# pi_day_2025.net
KiCad netlist of a schematic drawn in EAGLE
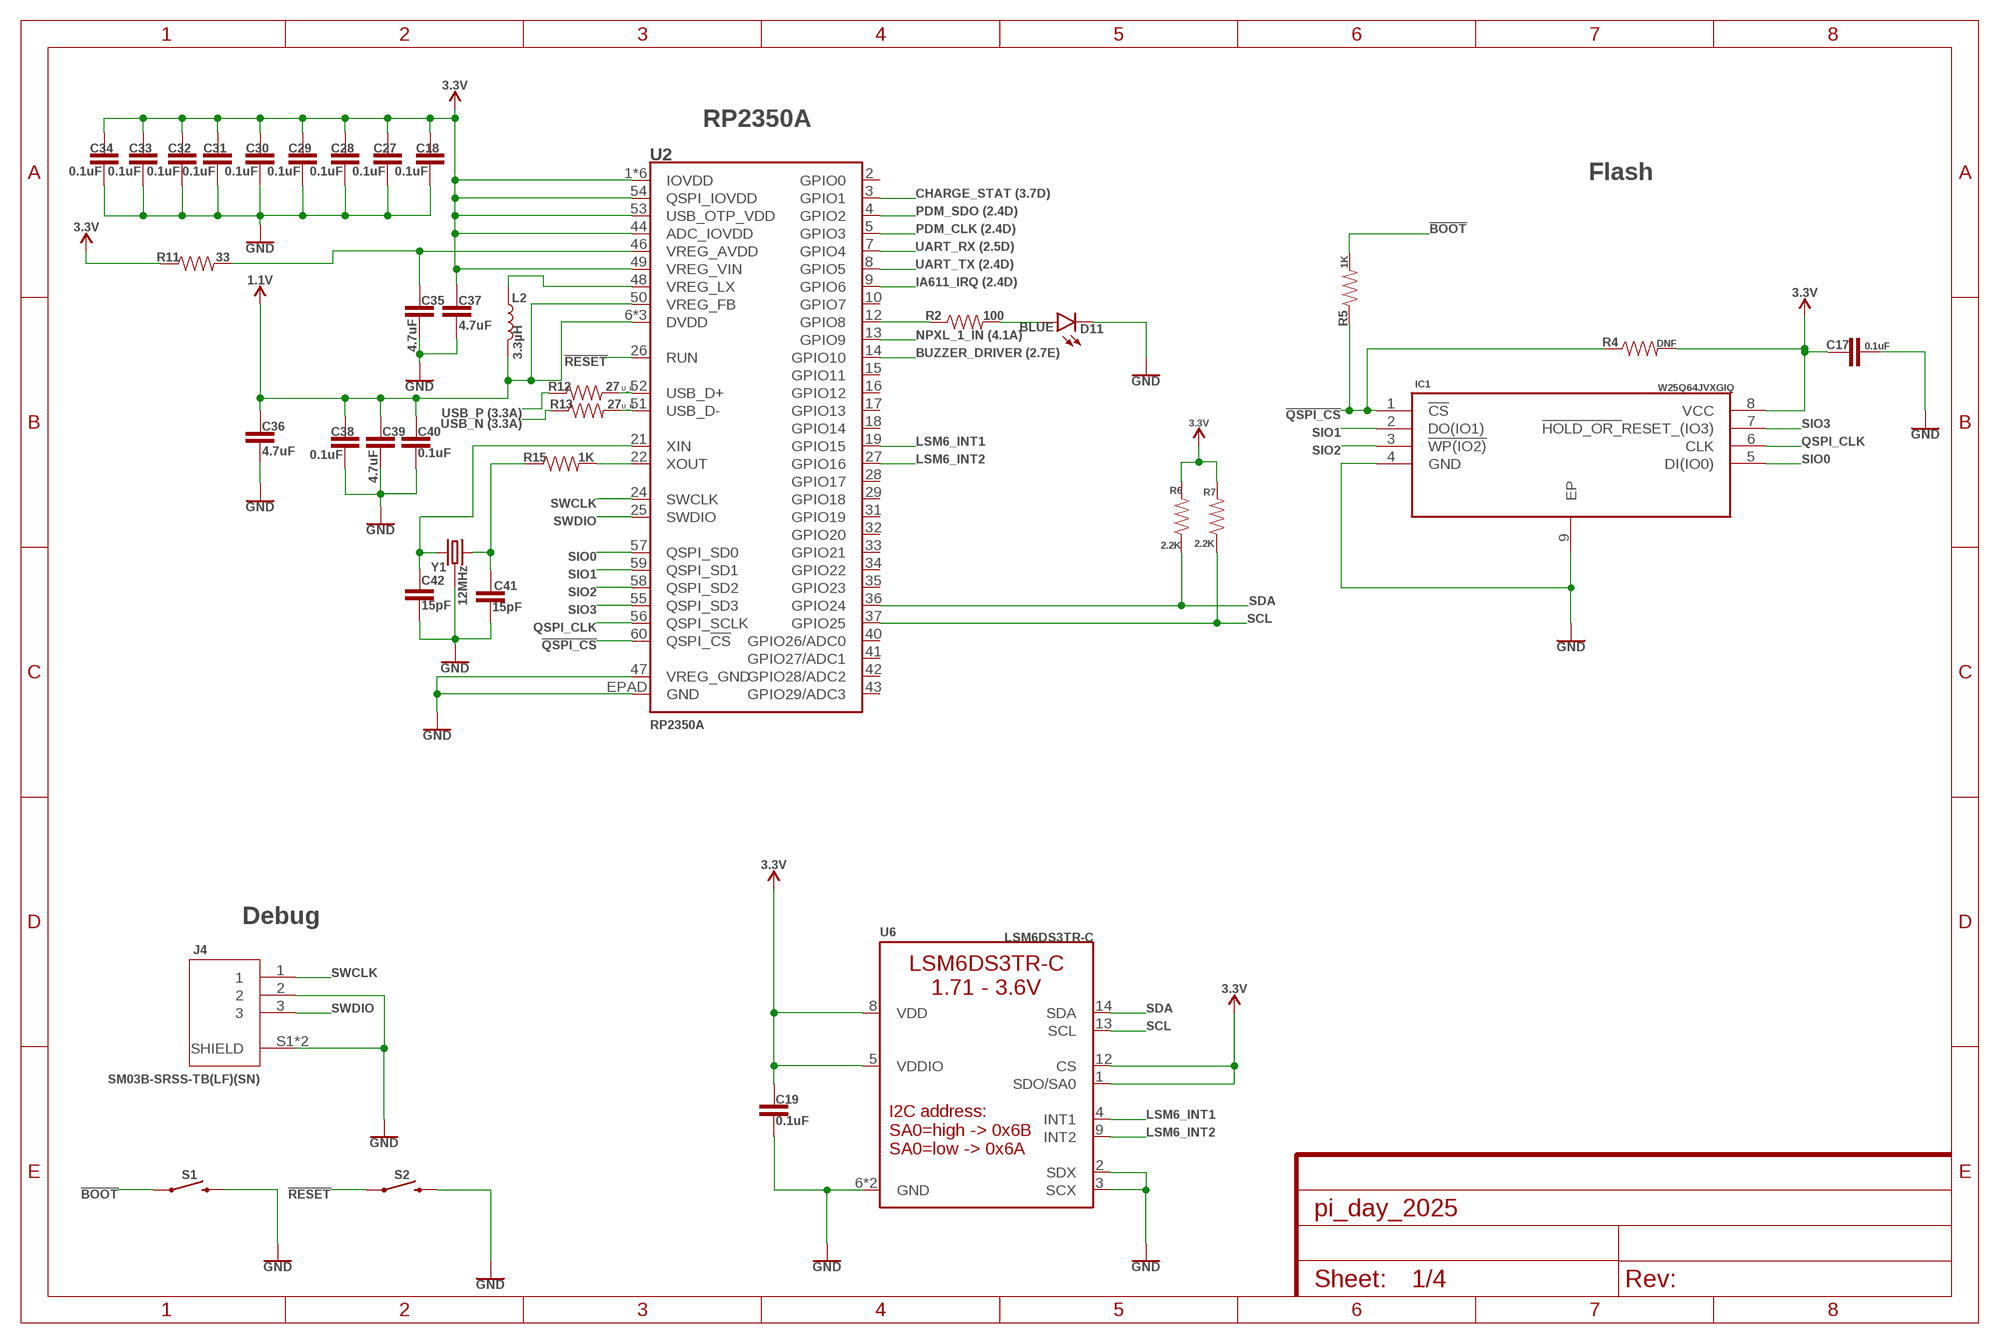
[diagram p0: schematic, sheet 1]
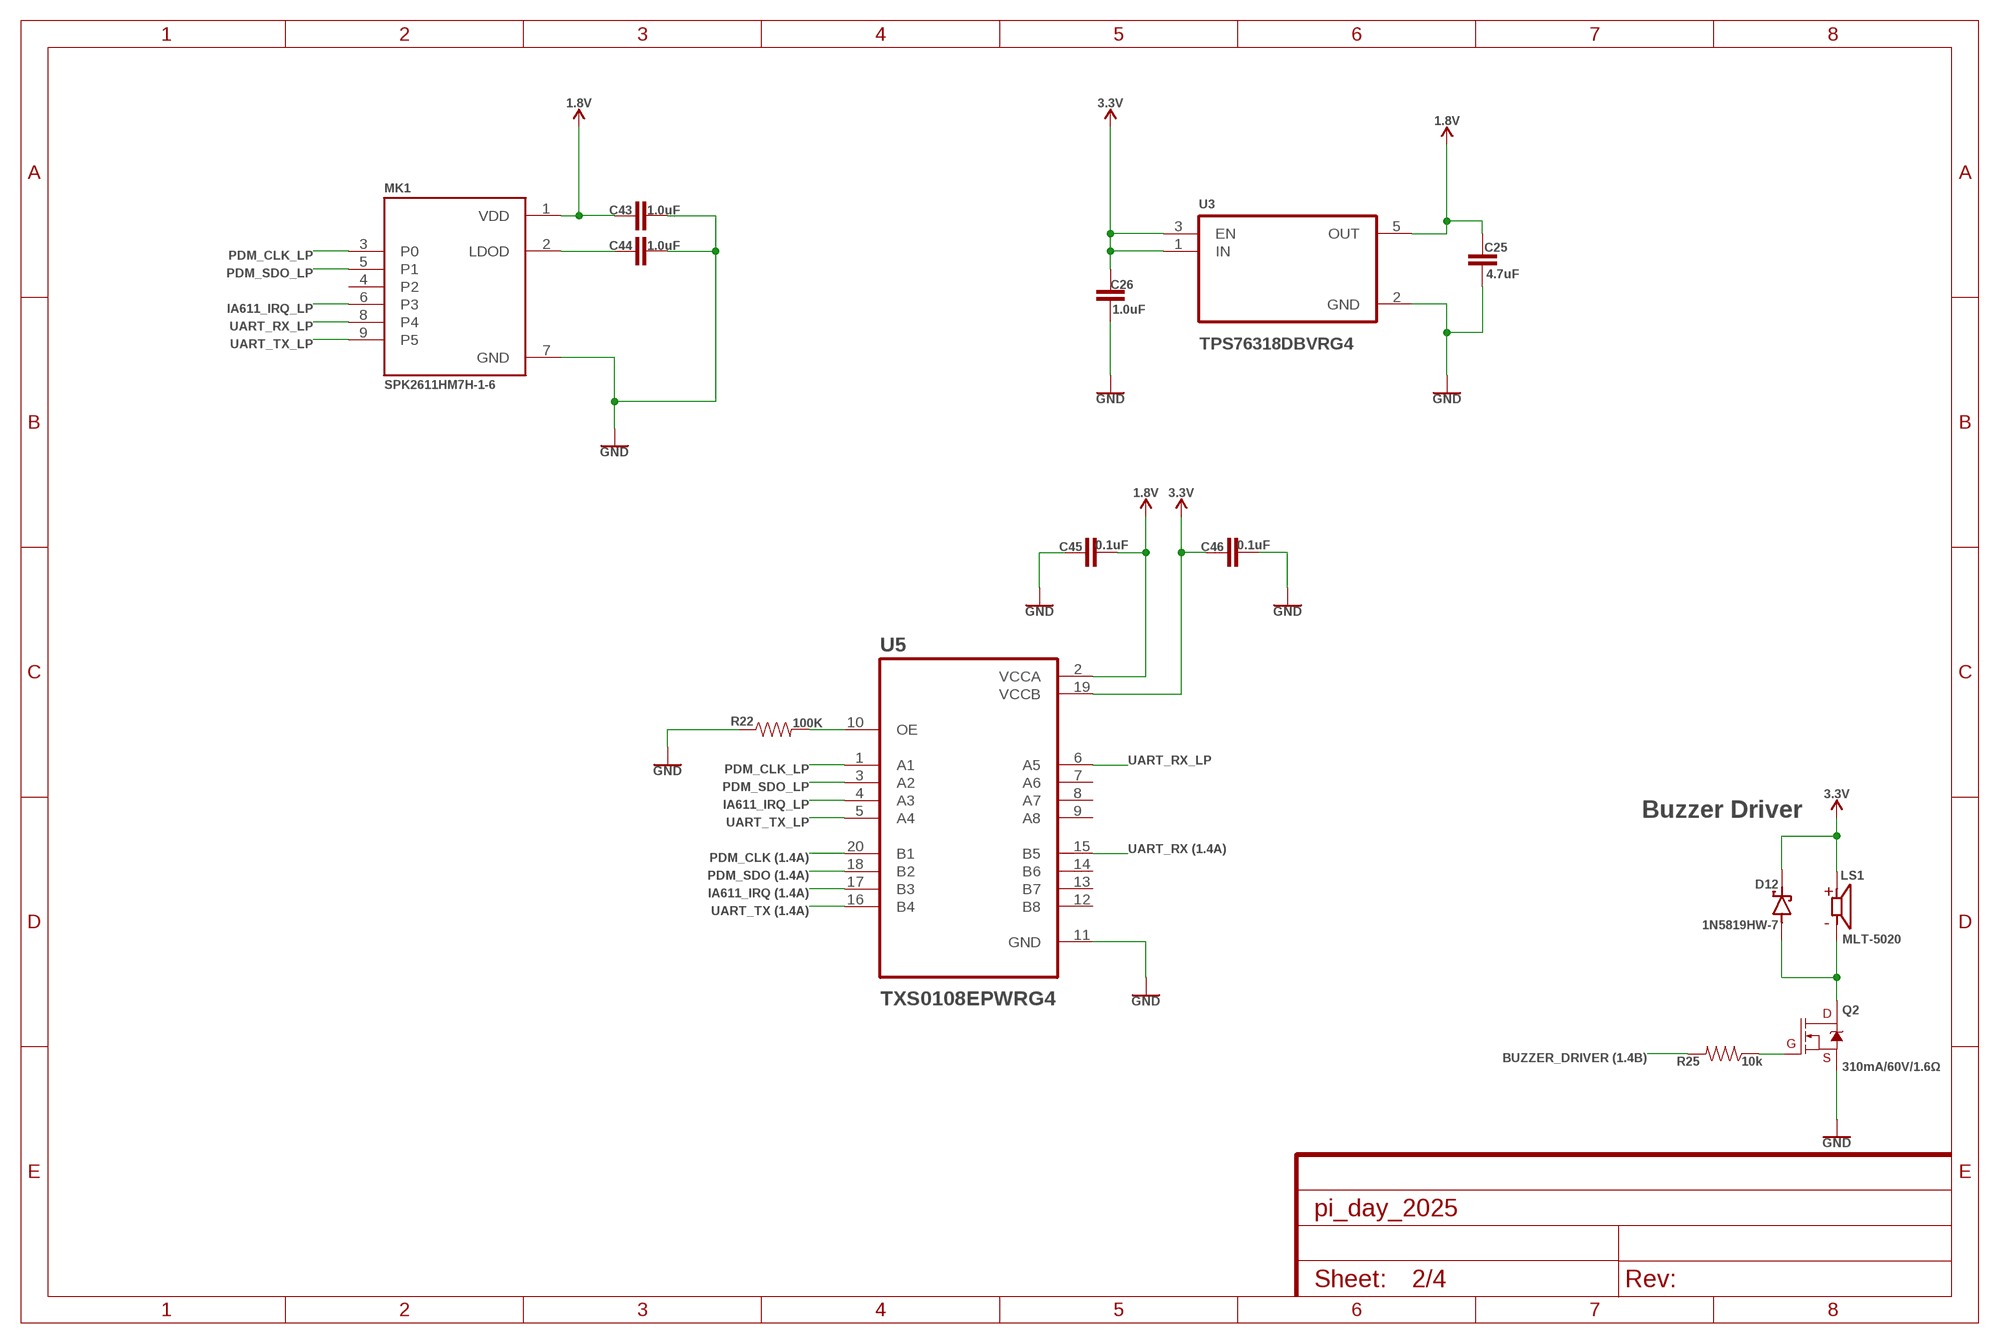
[diagram p1: schematic, sheet 2]
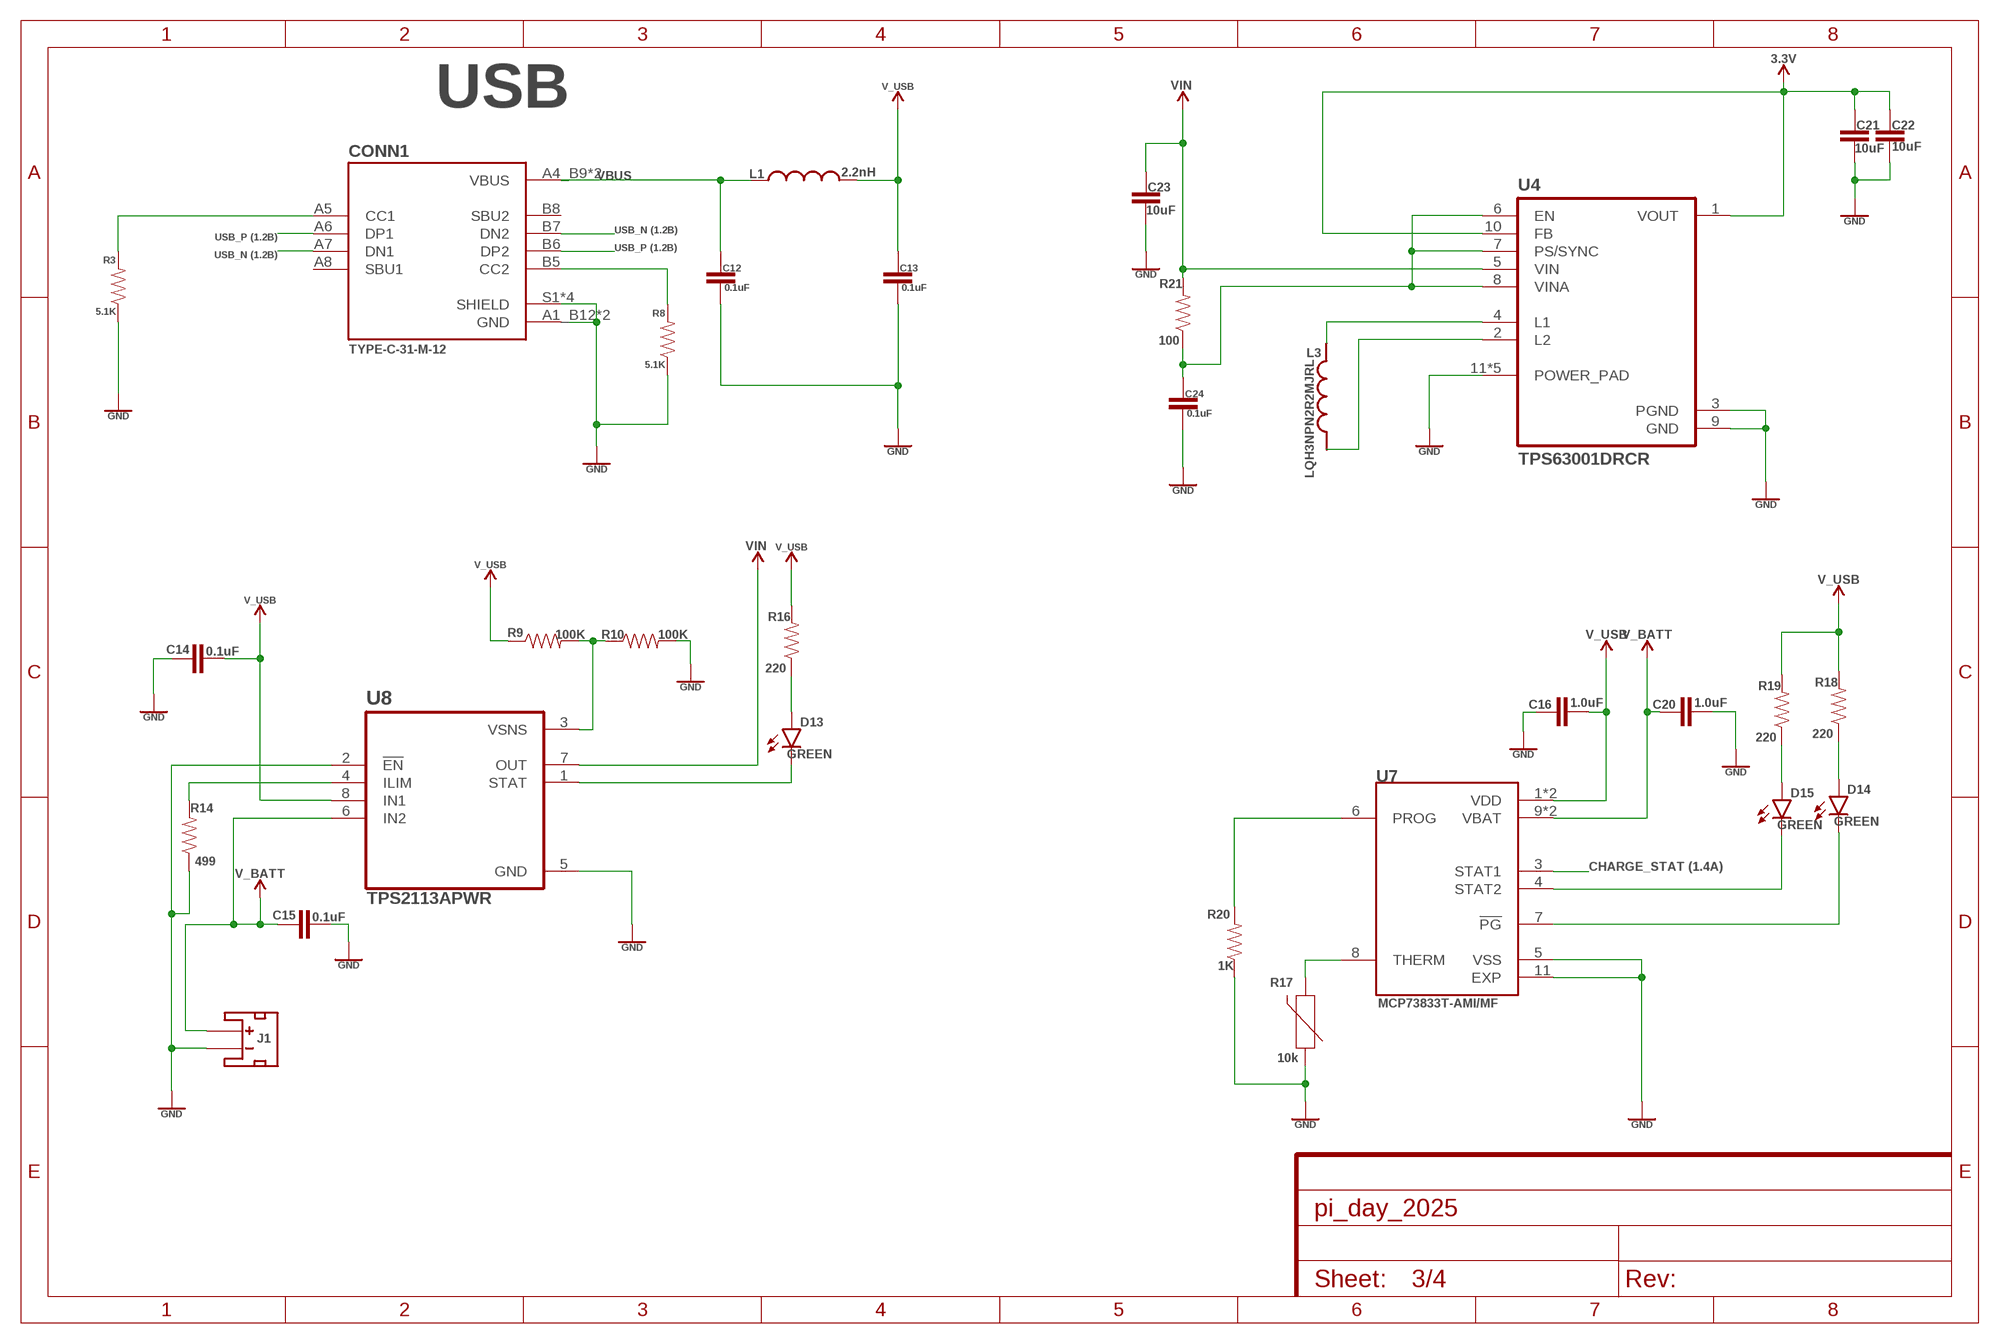
[diagram p2: schematic, sheet 3]
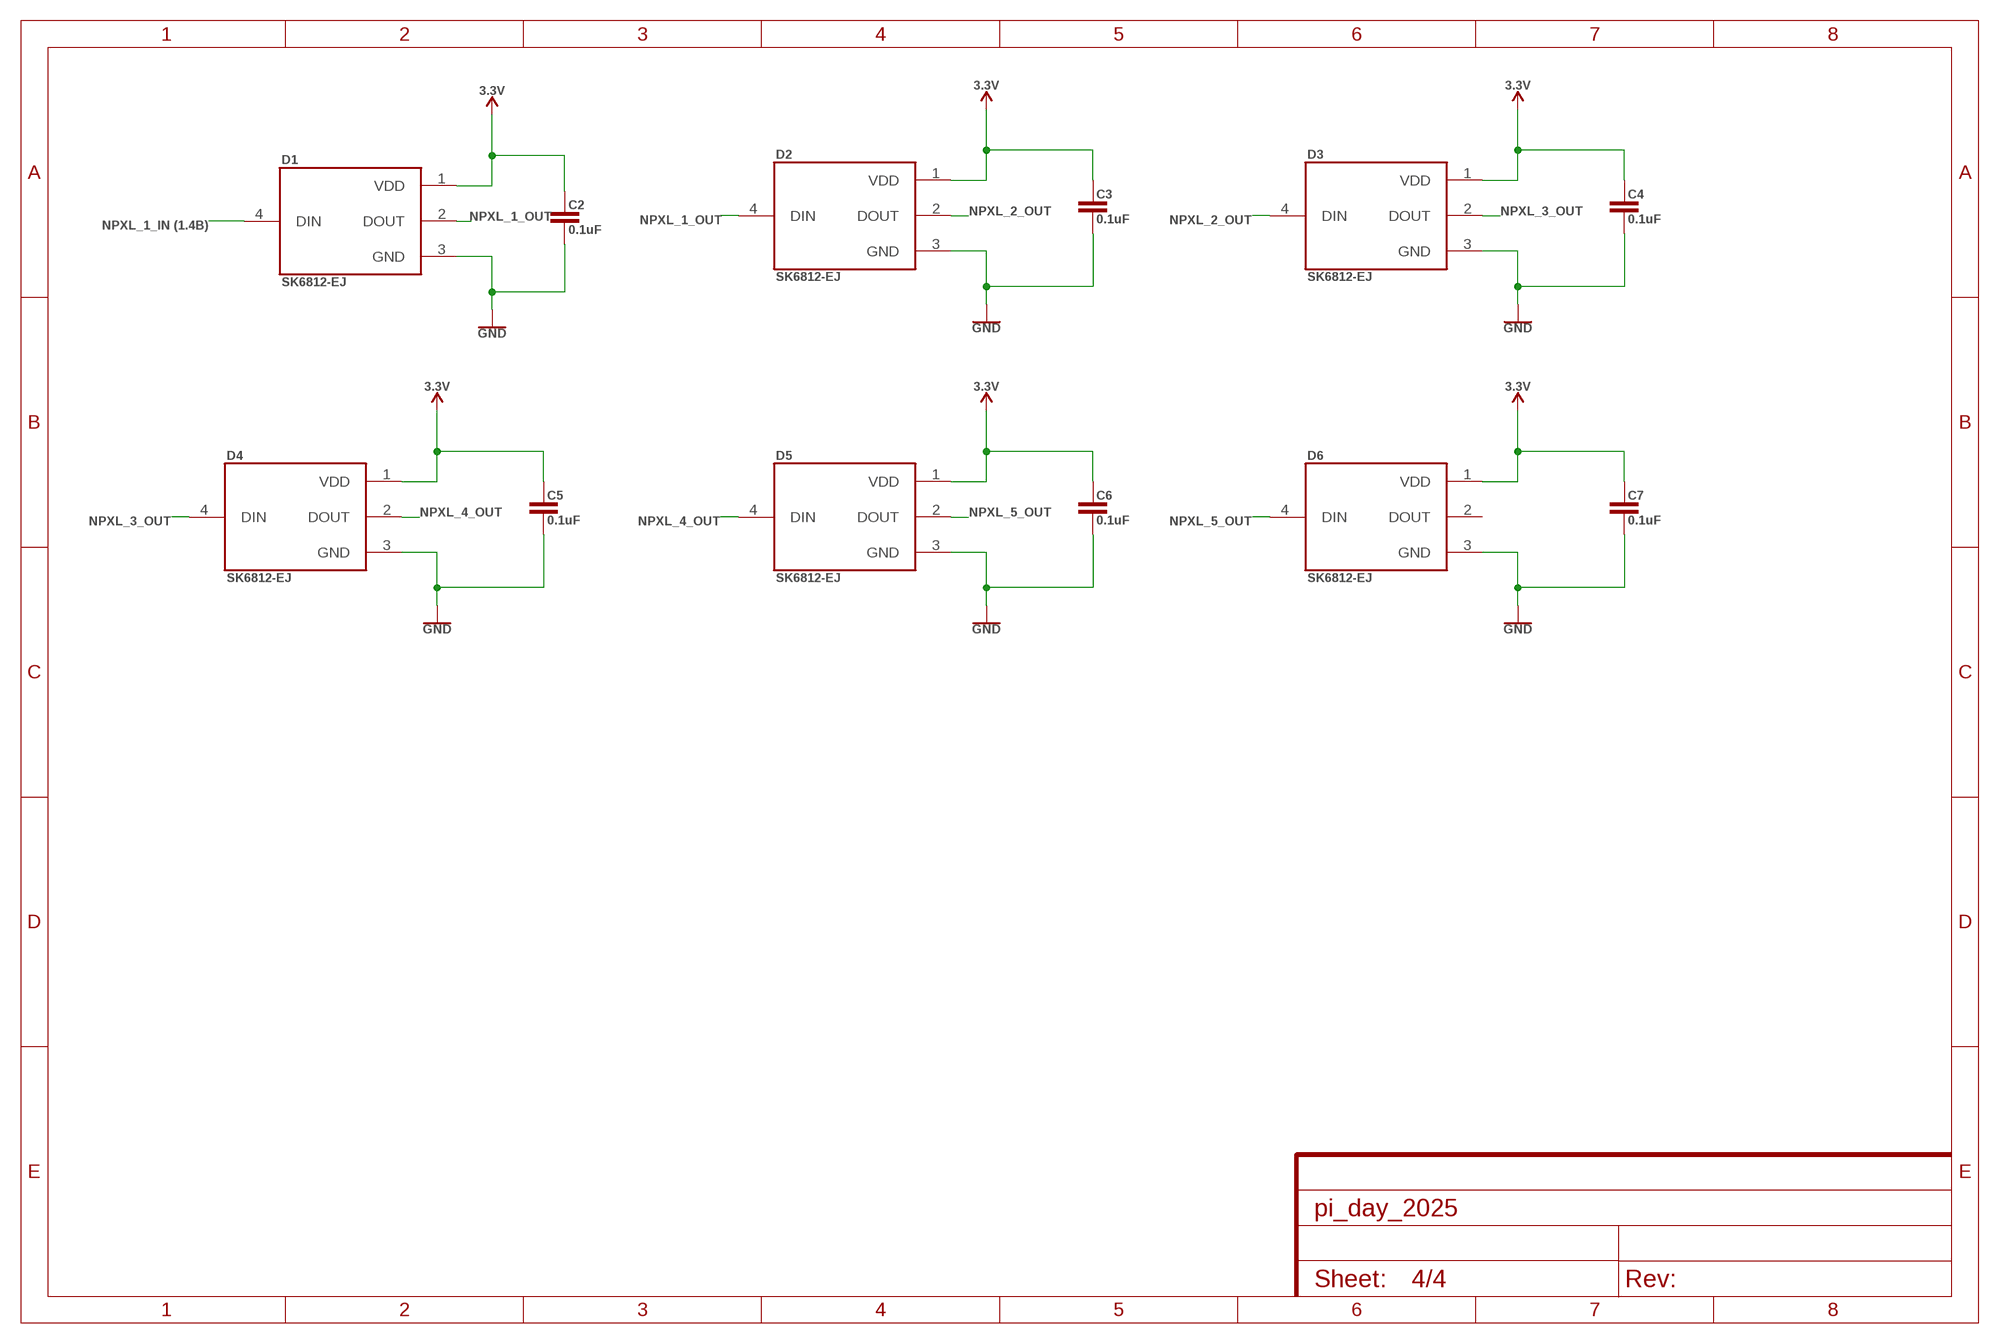
[diagram p3: schematic, sheet 4]

(export (version "E")
  (design (tool "Eeschema 10.0.6"))
  (components
    (comp (ref "C12")
      (value "0.1uF")
      (footprint "eagle-import:0402")
      (libsource (lib "eagle-import") (part "0.1UF-0402-16V-10%"))
    )
    (comp (ref "C13")
      (value "0.1uF")
      (footprint "eagle-import:0402")
      (libsource (lib "eagle-import") (part "0.1UF-0402-16V-10%"))
    )
    (comp (ref "C14")
      (value "0.1uF")
      (footprint "eagle-import:0402")
      (libsource (lib "eagle-import") (part "0.1UF-0402-10V-10%-X7R"))
    )
    (comp (ref "C15")
      (value "0.1uF")
      (footprint "eagle-import:0402")
      (libsource (lib "eagle-import") (part "0.1UF-0402-10V-10%-X7R"))
    )
    (comp (ref "C16")
      (value "1.0uF")
      (footprint "eagle-import:0402")
      (libsource (lib "eagle-import") (part "1.0UF-0402-16V-10%"))
    )
    (comp (ref "C20")
      (value "1.0uF")
      (footprint "eagle-import:0402")
      (libsource (lib "eagle-import") (part "1.0UF-0402-16V-10%"))
    )
    (comp (ref "C21")
      (value "10uF")
      (footprint "eagle-import:0402-TIGHT")
      (libsource (lib "eagle-import") (part "10UF-0402T-6.3V-20%"))
    )
    (comp (ref "C22")
      (value "10uF")
      (footprint "eagle-import:0402-TIGHT")
      (libsource (lib "eagle-import") (part "10UF-0402T-6.3V-20%"))
    )
    (comp (ref "C23")
      (value "10uF")
      (footprint "eagle-import:0402-TIGHT")
      (libsource (lib "eagle-import") (part "10UF-0402T-6.3V-20%"))
    )
    (comp (ref "C24")
      (value "0.1uF")
      (footprint "eagle-import:0402")
      (libsource (lib "eagle-import") (part "0.1UF-0402-16V-10%"))
    )
    (comp (ref "CONN1")
      (value "TYPE-C-31-M-12")
      (footprint "eagle-import:HRO_TYPE-C-31-M-12")
      (fields (field (name "MF") "HRO Electronics Co., Ltd."))
      (libsource (lib "eagle-import") (part "TYPE-C-31-M-12"))
    )
    (comp (ref "D13")
      (value "GREEN")
      (footprint "eagle-import:LED-0603")
      (libsource (lib "eagle-import") (part "LED-GREEN0603"))
    )
    (comp (ref "D14")
      (value "GREEN")
      (footprint "eagle-import:LED-0603")
      (libsource (lib "eagle-import") (part "LED-GREEN0603"))
    )
    (comp (ref "D15")
      (value "GREEN")
      (footprint "eagle-import:LED-0603")
      (libsource (lib "eagle-import") (part "LED-GREEN0603"))
    )
    (comp (ref "J1")
      (value "JST_2MM_MALE")
      (footprint "eagle-import:JST-2-SMD")
      (libsource (lib "eagle-import") (part "JST_2MM_MALE"))
    )
    (comp (ref "L1")
      (value "2.2nH")
      (footprint "eagle-import:INDC1608X100N")
      (fields (field (name "MF") "Murata") (field (name "MP") "LQW18AN2N2D10D"))
      (libsource (lib "eagle-import") (part "LQW18AN2N2D10D"))
    )
    (comp (ref "L3")
      (value "LQH3NPN2R2MJRL")
      (footprint "eagle-import:IND_LQH3NPN2R2MJRL")
      (fields (field (name "MF") "Murata"))
      (libsource (lib "eagle-import") (part "LQH3NPN2R2MJRL"))
    )
    (comp (ref "R3")
      (value "5.1K")
      (footprint "eagle-import:0402@1")
      (libsource (lib "eagle-import") (part "RESISTOR0402"))
    )
    (comp (ref "R8")
      (value "5.1K")
      (footprint "eagle-import:0402@1")
      (libsource (lib "eagle-import") (part "RESISTOR0402"))
    )
    (comp (ref "R9")
      (value "100K")
      (footprint "eagle-import:0402@1")
      (libsource (lib "eagle-import") (part "100KOHM-0402-1/16W-1%"))
    )
    (comp (ref "R10")
      (value "100K")
      (footprint "eagle-import:0402@1")
      (libsource (lib "eagle-import") (part "100KOHM-0402-1/16W-1%"))
    )
    (comp (ref "R14")
      (value "499")
      (footprint "eagle-import:0402@1")
      (libsource (lib "eagle-import") (part "RESISTOR0402"))
    )
    (comp (ref "R16")
      (value "220")
      (footprint "eagle-import:0402-TIGHT")
      (libsource (lib "eagle-import") (part "220OHM-0402-TIGHT-1/16W-1%"))
    )
    (comp (ref "R17")
      (value "10k")
      (footprint "eagle-import:0603")
      (libsource (lib "eagle-import") (part "NTC-THERMISTOR-0603"))
    )
    (comp (ref "R18")
      (value "220")
      (footprint "eagle-import:0402-TIGHT")
      (libsource (lib "eagle-import") (part "220OHM-0402-TIGHT-1/16W-1%"))
    )
    (comp (ref "R19")
      (value "220")
      (footprint "eagle-import:0402-TIGHT")
      (libsource (lib "eagle-import") (part "220OHM-0402-TIGHT-1/16W-1%"))
    )
    (comp (ref "R20")
      (value "1K")
      (footprint "eagle-import:0402@1")
      (libsource (lib "eagle-import") (part "1KOHM-0402-1/16W-1%"))
    )
    (comp (ref "R21")
      (value "100")
      (footprint "eagle-import:0402-TIGHT")
      (libsource (lib "eagle-import") (part "100OHM-0402-TIGHT-1/16W-1%"))
    )
    (comp (ref "U4")
      (value "TPS63001DRCR")
      (footprint "eagle-import:VREG_V62_16624-01YE")
      (fields (field (name "MF") "Texas Instruments"))
      (libsource (lib "eagle-import") (part "TPS63001DRCR"))
    )
    (comp (ref "U7")
      (value "MCP73833T-AMI/MF")
      (footprint "eagle-import:SON50P300X300X100-11N")
      (fields (field (name "MF") "Microchip"))
      (libsource (lib "eagle-import") (part "MCP73833T-AMI/MF"))
    )
    (comp (ref "U8")
      (value "TPS2113APWR")
      (footprint "eagle-import:SOP65P640X120-8N")
      (fields (field (name "MF") "Texas Instruments"))
      (libsource (lib "eagle-import") (part "TPS2113APWR"))
    )
    (comp (ref "C2")
      (value "0.1uF")
      (footprint "eagle-import:0402")
      (libsource (lib "eagle-import") (part "0.1UF-0402-10V-10%-X7R"))
    )
    (comp (ref "C3")
      (value "0.1uF")
      (footprint "eagle-import:0402")
      (libsource (lib "eagle-import") (part "0.1UF-0402-10V-10%-X7R"))
    )
    (comp (ref "C4")
      (value "0.1uF")
      (footprint "eagle-import:0402")
      (libsource (lib "eagle-import") (part "0.1UF-0402-10V-10%-X7R"))
    )
    (comp (ref "C5")
      (value "0.1uF")
      (footprint "eagle-import:0402")
      (libsource (lib "eagle-import") (part "0.1UF-0402-10V-10%-X7R"))
    )
    (comp (ref "C6")
      (value "0.1uF")
      (footprint "eagle-import:0402")
      (libsource (lib "eagle-import") (part "0.1UF-0402-10V-10%-X7R"))
    )
    (comp (ref "C7")
      (value "0.1uF")
      (footprint "eagle-import:0402")
      (libsource (lib "eagle-import") (part "0.1UF-0402-10V-10%-X7R"))
    )
    (comp (ref "D1")
      (value "SK6812-EJ")
      (footprint "eagle-import:LED_SK6812-E")
      (fields (field (name "MF") "DONGGUANG OPSCO OPTOELECTRONICS CO., LTD") (field (name "MP") "SK6812-E"))
      (libsource (lib "eagle-import") (part "SK6812-EJ"))
    )
    (comp (ref "D2")
      (value "SK6812-EJ")
      (footprint "eagle-import:LED_SK6812-E")
      (fields (field (name "MF") "DONGGUANG OPSCO OPTOELECTRONICS CO., LTD") (field (name "MP") "SK6812-E"))
      (libsource (lib "eagle-import") (part "SK6812-EJ"))
    )
    (comp (ref "D3")
      (value "SK6812-EJ")
      (footprint "eagle-import:LED_SK6812-E")
      (fields (field (name "MF") "DONGGUANG OPSCO OPTOELECTRONICS CO., LTD") (field (name "MP") "SK6812-E"))
      (libsource (lib "eagle-import") (part "SK6812-EJ"))
    )
    (comp (ref "D4")
      (value "SK6812-EJ")
      (footprint "eagle-import:LED_SK6812-E")
      (fields (field (name "MF") "DONGGUANG OPSCO OPTOELECTRONICS CO., LTD") (field (name "MP") "SK6812-E"))
      (libsource (lib "eagle-import") (part "SK6812-EJ"))
    )
    (comp (ref "D5")
      (value "SK6812-EJ")
      (footprint "eagle-import:LED_SK6812-E")
      (fields (field (name "MF") "DONGGUANG OPSCO OPTOELECTRONICS CO., LTD") (field (name "MP") "SK6812-E"))
      (libsource (lib "eagle-import") (part "SK6812-EJ"))
    )
    (comp (ref "D6")
      (value "SK6812-EJ")
      (footprint "eagle-import:LED_SK6812-E")
      (fields (field (name "MF") "DONGGUANG OPSCO OPTOELECTRONICS CO., LTD") (field (name "MP") "SK6812-E"))
      (libsource (lib "eagle-import") (part "SK6812-EJ"))
    )
    (comp (ref "C25")
      (value "4.7uF")
      (footprint "eagle-import:0402-TIGHT")
      (libsource (lib "eagle-import") (part "4.7UF-0402_TIGHT-6.3V-20%-X5R"))
    )
    (comp (ref "C26")
      (value "1.0uF")
      (footprint "eagle-import:0402")
      (libsource (lib "eagle-import") (part "1.0UF-0402-16V-10%"))
    )
    (comp (ref "C43")
      (value "1.0uF")
      (footprint "eagle-import:0402")
      (libsource (lib "eagle-import") (part "1.0UF-0402-16V-10%"))
    )
    (comp (ref "C44")
      (value "1.0uF")
      (footprint "eagle-import:0402")
      (libsource (lib "eagle-import") (part "1.0UF-0402-16V-10%"))
    )
    (comp (ref "C45")
      (value "0.1uF")
      (footprint "eagle-import:0402")
      (libsource (lib "eagle-import") (part "0.1UF-0402-6.3V-10%-X7R"))
    )
    (comp (ref "C46")
      (value "0.1uF")
      (footprint "eagle-import:0402")
      (libsource (lib "eagle-import") (part "0.1UF-0402-6.3V-10%-X7R"))
    )
    (comp (ref "D12")
      (value "1N5819HW-7")
      (footprint "eagle-import:SOD3715X145N")
      (fields (field (name "MF") "Diodes Inc."))
      (libsource (lib "eagle-import") (part "1N5819HW-7"))
    )
    (comp (ref "LS1")
      (value "MLT-5020")
      (footprint "eagle-import:CUI_CSS-0575A-SMT")
      (fields (field (name "MF") "CUI") (field (name "MP") "CSS-0575A-SMT"))
      (libsource (lib "eagle-import") (part "CSS-0575A-SMT"))
    )
    (comp (ref "MK1")
      (value "SPK2611HM7H-1-6")
      (footprint "eagle-import:MIC_SPK2611HM7H-1-6")
      (fields (field (name "MF") "Knowles"))
      (libsource (lib "eagle-import") (part "SPK2611HM7H-1-6"))
    )
    (comp (ref "Q2")
      (value "310mA/60V/1.6Ω")
      (footprint "eagle-import:SOT323")
      (libsource (lib "eagle-import") (part "MOSFET-NCH-2N7002PW"))
    )
    (comp (ref "R22")
      (value "100K")
      (footprint "eagle-import:0402@1")
      (libsource (lib "eagle-import") (part "100KOHM-0402-1/16W-1%"))
    )
    (comp (ref "R25")
      (value "10k")
      (footprint "eagle-import:0402")
      (libsource (lib "eagle-import") (part "10KOHM-0402-1/16W-1%"))
    )
    (comp (ref "U3")
      (value "TPS76318DBVRG4")
      (footprint "eagle-import:SOT95P280X145-5N")
      (fields
        (field (name "DIGIKEY_PART_NUMBER") "TPS76318DBVRG4-ND")
        (field (name "MF") "Texas Instruments")
      )
      (libsource (lib "eagle-import") (part "TPS76318DBVRG4"))
    )
    (comp (ref "U5")
      (value "TXS0108EPWRG4")
      (footprint "eagle-import:SOP65P640X120-20N")
      (fields (field (name "DIGIKEY_PART_NUMBER") "296-46258-2-ND") (field (name "MF") "Texas Instruments"))
      (libsource (lib "eagle-import") (part "TXS0108EPWRG4"))
    )
    (comp (ref "C17")
      (value "0.1uF")
      (footprint "eagle-import:0402")
      (libsource (lib "eagle-import") (part "0.1UF-0402-16V-10%"))
    )
    (comp (ref "C18")
      (value "0.1uF")
      (footprint "eagle-import:0402-TIGHT")
      (libsource (lib "eagle-import") (part "0.1UF-0402T-16V-10%-X7R-WE"))
    )
    (comp (ref "C19")
      (value "0.1uF")
      (footprint "eagle-import:0402-TIGHT")
      (libsource (lib "eagle-import") (part "0.1UF-0402T-16V-10%-X7R-WE"))
    )
    (comp (ref "C27")
      (value "0.1uF")
      (footprint "eagle-import:0402-TIGHT")
      (libsource (lib "eagle-import") (part "0.1UF-0402T-16V-10%-X7R-WE"))
    )
    (comp (ref "C28")
      (value "0.1uF")
      (footprint "eagle-import:0402-TIGHT")
      (libsource (lib "eagle-import") (part "0.1UF-0402T-16V-10%-X7R-WE"))
    )
    (comp (ref "C29")
      (value "0.1uF")
      (footprint "eagle-import:0402-TIGHT")
      (libsource (lib "eagle-import") (part "0.1UF-0402T-16V-10%-X7R-WE"))
    )
    (comp (ref "C30")
      (value "0.1uF")
      (footprint "eagle-import:0402-TIGHT")
      (libsource (lib "eagle-import") (part "0.1UF-0402T-16V-10%-X7R-WE"))
    )
    (comp (ref "C31")
      (value "0.1uF")
      (footprint "eagle-import:0402-TIGHT")
      (libsource (lib "eagle-import") (part "0.1UF-0402T-16V-10%-X7R-WE"))
    )
    (comp (ref "C32")
      (value "0.1uF")
      (footprint "eagle-import:0402-TIGHT")
      (libsource (lib "eagle-import") (part "0.1UF-0402T-16V-10%-X7R-WE"))
    )
    (comp (ref "C33")
      (value "0.1uF")
      (footprint "eagle-import:0402-TIGHT")
      (libsource (lib "eagle-import") (part "0.1UF-0402T-16V-10%-X7R-WE"))
    )
    (comp (ref "C34")
      (value "0.1uF")
      (footprint "eagle-import:0402-TIGHT")
      (libsource (lib "eagle-import") (part "0.1UF-0402T-16V-10%-X7R-WE"))
    )
    (comp (ref "C35")
      (value "4.7uF")
      (footprint "eagle-import:0402-TIGHT")
      (libsource (lib "eagle-import") (part "4.7UF-0402_TIGHT-6.3V-20%-X5R"))
    )
    (comp (ref "C36")
      (value "4.7uF")
      (footprint "eagle-import:0402-TIGHT")
      (libsource (lib "eagle-import") (part "4.7UF-0402_TIGHT-6.3V-20%-X5R"))
    )
    (comp (ref "C37")
      (value "4.7uF")
      (footprint "eagle-import:0402-TIGHT")
      (libsource (lib "eagle-import") (part "4.7UF-0402_TIGHT-6.3V-20%-X5R"))
    )
    (comp (ref "C38")
      (value "0.1uF")
      (footprint "eagle-import:0402-TIGHT")
      (libsource (lib "eagle-import") (part "0.1UF-0402T-16V-10%-X7R-WE"))
    )
    (comp (ref "C39")
      (value "4.7uF")
      (footprint "eagle-import:0402-TIGHT")
      (libsource (lib "eagle-import") (part "4.7UF-0402_TIGHT-6.3V-20%-X5R"))
    )
    (comp (ref "C40")
      (value "0.1uF")
      (footprint "eagle-import:0402-TIGHT")
      (libsource (lib "eagle-import") (part "0.1UF-0402T-16V-10%-X7R-WE"))
    )
    (comp (ref "C41")
      (value "15pF")
      (footprint "eagle-import:0402")
      (libsource (lib "eagle-import") (part "15PF-0402-50V-5%"))
    )
    (comp (ref "C42")
      (value "15pF")
      (footprint "eagle-import:0402")
      (libsource (lib "eagle-import") (part "15PF-0402-50V-5%"))
    )
    (comp (ref "D11")
      (value "BLUE")
      (footprint "eagle-import:LED-0603")
      (libsource (lib "eagle-import") (part "LED-BLUE0603"))
    )
    (comp (ref "IC1")
      (value "W25Q64JVXGIQ")
      (footprint "eagle-import:SON80P400X400X50-9N")
      (libsource (lib "eagle-import") (part "W25Q64JVXGIQ"))
    )
    (comp (ref "J4")
      (value "SM03B-SRSS-TB(LF)(SN)")
      (footprint "eagle-import:JST_SM03B-SRSS-TB(LF)(SN)")
      (fields (field (name "MF") "JST Sales America Inc."))
      (libsource (lib "eagle-import") (part "SM03B-SRSS-TB(LF)(SN)"))
    )
    (comp (ref "L2")
      (value "3.3µH")
      (footprint "eagle-import:0805")
      (libsource (lib "eagle-import") (part "INDUCTOR-0805-3.3UH"))
    )
    (comp (ref "R2")
      (value "100")
      (footprint "eagle-import:0402-TIGHT")
      (libsource (lib "eagle-import") (part "100OHM-0402-TIGHT-1/16W-1%"))
    )
    (comp (ref "R4")
      (value "DNF")
      (footprint "eagle-import:0402@1")
      (libsource (lib "eagle-import") (part "RESISTOR0402"))
    )
    (comp (ref "R5")
      (value "1K")
      (footprint "eagle-import:0402@1")
      (libsource (lib "eagle-import") (part "RESISTOR0402"))
    )
    (comp (ref "R6")
      (value "2.2K")
      (footprint "eagle-import:0402@1")
      (libsource (lib "eagle-import") (part "RESISTOR0402"))
    )
    (comp (ref "R7")
      (value "2.2K")
      (footprint "eagle-import:0402@1")
      (libsource (lib "eagle-import") (part "RESISTOR0402"))
    )
    (comp (ref "R11")
      (value "33")
      (footprint "eagle-import:0402@1")
      (libsource (lib "eagle-import") (part "33OHM-0402-1/10W-1%"))
    )
    (comp (ref "R12")
      (value "27")
      (footprint "eagle-import:0402-TIGHT")
      (libsource (lib "eagle-import") (part "27OHM"))
    )
    (comp (ref "R13")
      (value "27")
      (footprint "eagle-import:0402-TIGHT")
      (libsource (lib "eagle-import") (part "27OHM"))
    )
    (comp (ref "R15")
      (value "1K")
      (footprint "eagle-import:0402@1")
      (libsource (lib "eagle-import") (part "1KOHM-0402-1/16W-1%"))
    )
    (comp (ref "S1")
      (value "MOMENTARY-SWITCH-SPST-SMD-4.6X2.8MM")
      (footprint "eagle-import:TACTILE_SWITCH_SMD_4.6X2.8MM")
      (libsource (lib "eagle-import") (part "MOMENTARY-SWITCH-SPST-SMD-4.6X2.8MM"))
    )
    (comp (ref "S2")
      (value "MOMENTARY-SWITCH-SPST-SMD-4.6X2.8MM")
      (footprint "eagle-import:TACTILE_SWITCH_SMD_4.6X2.8MM")
      (libsource (lib "eagle-import") (part "MOMENTARY-SWITCH-SPST-SMD-4.6X2.8MM"))
    )
    (comp (ref "U2")
      (value "RP2350A")
      (footprint "eagle-import:RP2350A")
      (libsource (lib "eagle-import") (part "RP2350A"))
    )
    (comp (ref "U6")
      (value "LSM6DS3TR-C")
      (footprint "eagle-import:LGA-14-2.5X3MM")
      (fields (field (name "MF") "STMicroelectronics"))
      (libsource (lib "eagle-import") (part "LSM6DS3TR-C"))
    )
    (comp (ref "Y1")
      (value "12MHz")
      (footprint "eagle-import:CRYSTAL-SMD-3.2X2.5MM")
      (libsource (lib "eagle-import") (part "CRYSTAL-GROUNDEDSMD-3.2X2.5"))
    )
  )
  (nets
    (net (code "1") (name "1.1V") (class "Default")
      (node (ref "C36") (pin "1") (pinfunction "1_1") (pintype "passive"))
      (node (ref "C38") (pin "1") (pinfunction "1_1") (pintype "passive"))
      (node (ref "C39") (pin "1") (pinfunction "1_1") (pintype "passive"))
      (node (ref "C40") (pin "1") (pinfunction "1_1") (pintype "passive"))
      (node (ref "L2") (pin "2") (pinfunction "2_2") (pintype "passive"))
      (node (ref "U2") (pin "23") (pinfunction "DVDD_23") (pintype "bidirectional"))
      (node (ref "U2") (pin "39") (pinfunction "DVDD_39") (pintype "bidirectional"))
      (node (ref "U2") (pin "50") (pinfunction "VREG_FB_50") (pintype "bidirectional"))
      (node (ref "U2") (pin "6") (pinfunction "DVDD_6") (pintype "bidirectional"))
    )
    (net (code "2") (name "1.8V") (class "Default")
      (node (ref "C25") (pin "1") (pinfunction "1_1") (pintype "passive"))
      (node (ref "C43") (pin "1") (pinfunction "1_1") (pintype "passive"))
      (node (ref "C45") (pin "2") (pinfunction "2_2") (pintype "passive"))
      (node (ref "MK1") (pin "1") (pinfunction "VDD_1") (pintype "power_in"))
      (node (ref "U3") (pin "5") (pinfunction "OUT_5") (pintype "output"))
      (node (ref "U5") (pin "2") (pinfunction "VCCA_2") (pintype "power_in"))
    )
    (net (code "3") (name "3.3V") (class "Default")
      (node (ref "C17") (pin "1") (pinfunction "1_1") (pintype "passive"))
      (node (ref "C18") (pin "1") (pinfunction "1_1") (pintype "passive"))
      (node (ref "C19") (pin "1") (pinfunction "1_1") (pintype "passive"))
      (node (ref "C2") (pin "1") (pinfunction "1_1") (pintype "passive"))
      (node (ref "C21") (pin "1") (pinfunction "1_1") (pintype "passive"))
      (node (ref "C22") (pin "1") (pinfunction "1_1") (pintype "passive"))
      (node (ref "C26") (pin "1") (pinfunction "1_1") (pintype "passive"))
      (node (ref "C27") (pin "1") (pinfunction "1_1") (pintype "passive"))
      (node (ref "C28") (pin "1") (pinfunction "1_1") (pintype "passive"))
      (node (ref "C29") (pin "1") (pinfunction "1_1") (pintype "passive"))
      (node (ref "C3") (pin "1") (pinfunction "1_1") (pintype "passive"))
      (node (ref "C30") (pin "1") (pinfunction "1_1") (pintype "passive"))
      (node (ref "C31") (pin "1") (pinfunction "1_1") (pintype "passive"))
      (node (ref "C32") (pin "1") (pinfunction "1_1") (pintype "passive"))
      (node (ref "C33") (pin "1") (pinfunction "1_1") (pintype "passive"))
      (node (ref "C34") (pin "1") (pinfunction "1_1") (pintype "passive"))
      (node (ref "C37") (pin "1") (pinfunction "1_1") (pintype "passive"))
      (node (ref "C4") (pin "1") (pinfunction "1_1") (pintype "passive"))
      (node (ref "C46") (pin "1") (pinfunction "1_1") (pintype "passive"))
      (node (ref "C5") (pin "1") (pinfunction "1_1") (pintype "passive"))
      (node (ref "C6") (pin "1") (pinfunction "1_1") (pintype "passive"))
      (node (ref "C7") (pin "1") (pinfunction "1_1") (pintype "passive"))
      (node (ref "D1") (pin "1") (pinfunction "VDD_1") (pintype "power_in"))
      (node (ref "D12") (pin "C") (pinfunction "K_C") (pintype "passive"))
      (node (ref "D2") (pin "1") (pinfunction "VDD_1") (pintype "power_in"))
      (node (ref "D3") (pin "1") (pinfunction "VDD_1") (pintype "power_in"))
      (node (ref "D4") (pin "1") (pinfunction "VDD_1") (pintype "power_in"))
      (node (ref "D5") (pin "1") (pinfunction "VDD_1") (pintype "power_in"))
      (node (ref "D6") (pin "1") (pinfunction "VDD_1") (pintype "power_in"))
      (node (ref "IC1") (pin "8") (pinfunction "VCC_8") (pintype "bidirectional"))
      (node (ref "LS1") (pin "1") (pinfunction "P_1") (pintype "passive"))
      (node (ref "R11") (pin "1") (pinfunction "1_1") (pintype "passive"))
      (node (ref "R4") (pin "2") (pinfunction "2_2") (pintype "passive"))
      (node (ref "R6") (pin "2") (pinfunction "2_2") (pintype "passive"))
      (node (ref "R7") (pin "2") (pinfunction "2_2") (pintype "passive"))
      (node (ref "U2") (pin "1") (pinfunction "IOVDD_1") (pintype "bidirectional"))
      (node (ref "U2") (pin "11") (pinfunction "IOVDD_11") (pintype "bidirectional"))
      (node (ref "U2") (pin "20") (pinfunction "IOVDD_20") (pintype "bidirectional"))
      (node (ref "U2") (pin "30") (pinfunction "IOVDD_30") (pintype "bidirectional"))
      (node (ref "U2") (pin "38") (pinfunction "IOVDD_38") (pintype "bidirectional"))
      (node (ref "U2") (pin "44") (pinfunction "ADC_IOVDD_44") (pintype "bidirectional"))
      (node (ref "U2") (pin "45") (pinfunction "IOVDD_45") (pintype "bidirectional"))
      (node (ref "U2") (pin "49") (pinfunction "VREG_VIN_49") (pintype "bidirectional"))
      (node (ref "U2") (pin "53") (pinfunction "USB_OTP_VDD_53") (pintype "bidirectional"))
      (node (ref "U2") (pin "54") (pinfunction "QSPI_IOVDD_54") (pintype "bidirectional"))
      (node (ref "U3") (pin "1") (pinfunction "IN_1") (pintype "input"))
      (node (ref "U3") (pin "3") (pinfunction "EN_3") (pintype "input"))
      (node (ref "U4") (pin "1") (pinfunction "VOUT_1") (pintype "output"))
      (node (ref "U4") (pin "10") (pinfunction "FB_10") (pintype "input"))
      (node (ref "U5") (pin "19") (pinfunction "VCCB_19") (pintype "power_in"))
      (node (ref "U6") (pin "1") (pinfunction "SDO/SA0_1") (pintype "bidirectional"))
      (node (ref "U6") (pin "12") (pinfunction "CS_12") (pintype "bidirectional"))
      (node (ref "U6") (pin "5") (pinfunction "VDDIO_5") (pintype "bidirectional"))
      (node (ref "U6") (pin "8") (pinfunction "VDD_8") (pintype "bidirectional"))
    )
    (net (code "4") (name "BUZZER_DRIVER") (class "Default")
      (node (ref "R25") (pin "2") (pinfunction "2_2") (pintype "passive"))
      (node (ref "U2") (pin "14") (pinfunction "GPIO10_14") (pintype "bidirectional"))
    )
    (net (code "5") (name "CHARGE_STAT") (class "Default")
      (node (ref "U2") (pin "3") (pinfunction "GPIO1_3") (pintype "bidirectional"))
      (node (ref "U7") (pin "3") (pinfunction "STAT1_3") (pintype "output"))
    )
    (net (code "6") (name "GND") (class "Default")
      (node (ref "C12") (pin "2") (pinfunction "2_2") (pintype "passive"))
      (node (ref "C13") (pin "2") (pinfunction "2_2") (pintype "passive"))
      (node (ref "C14") (pin "1") (pinfunction "1_1") (pintype "passive"))
      (node (ref "C15") (pin "2") (pinfunction "2_2") (pintype "passive"))
      (node (ref "C16") (pin "1") (pinfunction "1_1") (pintype "passive"))
      (node (ref "C17") (pin "2") (pinfunction "2_2") (pintype "passive"))
      (node (ref "C18") (pin "2") (pinfunction "2_2") (pintype "passive"))
      (node (ref "C19") (pin "2") (pinfunction "2_2") (pintype "passive"))
      (node (ref "C2") (pin "2") (pinfunction "2_2") (pintype "passive"))
      (node (ref "C20") (pin "2") (pinfunction "2_2") (pintype "passive"))
      (node (ref "C21") (pin "2") (pinfunction "2_2") (pintype "passive"))
      (node (ref "C22") (pin "2") (pinfunction "2_2") (pintype "passive"))
      (node (ref "C23") (pin "2") (pinfunction "2_2") (pintype "passive"))
      (node (ref "C24") (pin "2") (pinfunction "2_2") (pintype "passive"))
      (node (ref "C25") (pin "2") (pinfunction "2_2") (pintype "passive"))
      (node (ref "C26") (pin "2") (pinfunction "2_2") (pintype "passive"))
      (node (ref "C27") (pin "2") (pinfunction "2_2") (pintype "passive"))
      (node (ref "C28") (pin "2") (pinfunction "2_2") (pintype "passive"))
      (node (ref "C29") (pin "2") (pinfunction "2_2") (pintype "passive"))
      (node (ref "C3") (pin "2") (pinfunction "2_2") (pintype "passive"))
      (node (ref "C30") (pin "2") (pinfunction "2_2") (pintype "passive"))
      (node (ref "C31") (pin "2") (pinfunction "2_2") (pintype "passive"))
      (node (ref "C32") (pin "2") (pinfunction "2_2") (pintype "passive"))
      (node (ref "C33") (pin "2") (pinfunction "2_2") (pintype "passive"))
      (node (ref "C34") (pin "2") (pinfunction "2_2") (pintype "passive"))
      (node (ref "C35") (pin "2") (pinfunction "2_2") (pintype "passive"))
      (node (ref "C36") (pin "2") (pinfunction "2_2") (pintype "passive"))
      (node (ref "C37") (pin "2") (pinfunction "2_2") (pintype "passive"))
      (node (ref "C38") (pin "2") (pinfunction "2_2") (pintype "passive"))
      (node (ref "C39") (pin "2") (pinfunction "2_2") (pintype "passive"))
      (node (ref "C4") (pin "2") (pinfunction "2_2") (pintype "passive"))
      (node (ref "C40") (pin "2") (pinfunction "2_2") (pintype "passive"))
      (node (ref "C41") (pin "2") (pinfunction "2_2") (pintype "passive"))
      (node (ref "C42") (pin "2") (pinfunction "2_2") (pintype "passive"))
      (node (ref "C43") (pin "2") (pinfunction "2_2") (pintype "passive"))
      (node (ref "C44") (pin "2") (pinfunction "2_2") (pintype "passive"))
      (node (ref "C45") (pin "1") (pinfunction "1_1") (pintype "passive"))
      (node (ref "C46") (pin "2") (pinfunction "2_2") (pintype "passive"))
      (node (ref "C5") (pin "2") (pinfunction "2_2") (pintype "passive"))
      (node (ref "C6") (pin "2") (pinfunction "2_2") (pintype "passive"))
      (node (ref "C7") (pin "2") (pinfunction "2_2") (pintype "passive"))
      (node (ref "CONN1") (pin "A1_B12") (pinfunction "GND_A1_B12") (pintype "power_in"))
      (node (ref "CONN1") (pin "B1_A12") (pinfunction "GND_B1_A12") (pintype "power_in"))
      (node (ref "CONN1") (pin "S1") (pinfunction "SHIELD_S1") (pintype "passive"))
      (node (ref "CONN1") (pin "S2") (pinfunction "SHIELD_S2") (pintype "passive"))
      (node (ref "CONN1") (pin "S3") (pinfunction "SHIELD_S3") (pintype "passive"))
      (node (ref "CONN1") (pin "S4") (pinfunction "SHIELD_S4") (pintype "passive"))
      (node (ref "D1") (pin "3") (pinfunction "GND_3") (pintype "power_in"))
      (node (ref "D11") (pin "C") (pinfunction "C_C") (pintype "passive"))
      (node (ref "D2") (pin "3") (pinfunction "GND_3") (pintype "power_in"))
      (node (ref "D3") (pin "3") (pinfunction "GND_3") (pintype "power_in"))
      (node (ref "D4") (pin "3") (pinfunction "GND_3") (pintype "power_in"))
      (node (ref "D5") (pin "3") (pinfunction "GND_3") (pintype "power_in"))
      (node (ref "D6") (pin "3") (pinfunction "GND_3") (pintype "power_in"))
      (node (ref "IC1") (pin "4") (pinfunction "GND_4") (pintype "bidirectional"))
      (node (ref "IC1") (pin "9") (pinfunction "EP_9") (pintype "bidirectional"))
      (node (ref "J1") (pin "1") (pinfunction "-_1") (pintype "bidirectional"))
      (node (ref "J4") (pin "2") (pinfunction "2_2") (pintype "passive"))
      (node (ref "J4") (pin "S1") (pinfunction "SHIELD_S1") (pintype "passive"))
      (node (ref "J4") (pin "S2") (pinfunction "SHIELD_S2") (pintype "passive"))
      (node (ref "MK1") (pin "7") (pinfunction "GND_7") (pintype "power_in"))
      (node (ref "Q2") (pin "2") (pinfunction "S_2") (pintype "bidirectional"))
      (node (ref "R10") (pin "2") (pinfunction "2_2") (pintype "passive"))
      (node (ref "R14") (pin "1") (pinfunction "1_1") (pintype "passive"))
      (node (ref "R17") (pin "1") (pinfunction "1_1") (pintype "bidirectional"))
      (node (ref "R20") (pin "1") (pinfunction "1_1") (pintype "passive"))
      (node (ref "R22") (pin "1") (pinfunction "1_1") (pintype "passive"))
      (node (ref "R3") (pin "1") (pinfunction "1_1") (pintype "passive"))
      (node (ref "R8") (pin "1") (pinfunction "1_1") (pintype "passive"))
      (node (ref "S1") (pin "3") (pinfunction "2_3") (pintype "passive"))
      (node (ref "S1") (pin "4") (pinfunction "2_4") (pintype "passive"))
      (node (ref "S2") (pin "3") (pinfunction "2_3") (pintype "passive"))
      (node (ref "S2") (pin "4") (pinfunction "2_4") (pintype "passive"))
      (node (ref "U2") (pin "47") (pinfunction "VREG_GND_47") (pintype "bidirectional"))
      (node (ref "U2") (pin "EPAD") (pinfunction "GND_EPAD") (pintype "bidirectional"))
      (node (ref "U3") (pin "2") (pinfunction "GND_2") (pintype "power_in"))
      (node (ref "U4") (pin "11") (pinfunction "POWER_PAD_11") (pintype "bidirectional"))
      (node (ref "U4") (pin "12") (pinfunction "POWER_PAD_12") (pintype "bidirectional"))
      (node (ref "U4") (pin "13") (pinfunction "POWER_PAD_13") (pintype "bidirectional"))
      (node (ref "U4") (pin "14") (pinfunction "POWER_PAD_14") (pintype "bidirectional"))
      (node (ref "U4") (pin "15") (pinfunction "POWER_PAD_15") (pintype "bidirectional"))
      (node (ref "U4") (pin "3") (pinfunction "PGND_3") (pintype "power_in"))
      (node (ref "U4") (pin "9") (pinfunction "GND_9") (pintype "power_in"))
      (node (ref "U5") (pin "11") (pinfunction "GND_11") (pintype "power_in"))
      (node (ref "U6") (pin "2") (pinfunction "SDX_2") (pintype "bidirectional"))
      (node (ref "U6") (pin "3") (pinfunction "SCX_3") (pintype "bidirectional"))
      (node (ref "U6") (pin "6") (pinfunction "GND_6") (pintype "bidirectional"))
      (node (ref "U6") (pin "7") (pinfunction "GND_7") (pintype "bidirectional"))
      (node (ref "U7") (pin "11") (pinfunction "EXP_11") (pintype "passive"))
      (node (ref "U7") (pin "5") (pinfunction "VSS_5") (pintype "power_in"))
      (node (ref "U8") (pin "2") (pinfunction "~{EN}_2") (pintype "input"))
      (node (ref "U8") (pin "5") (pinfunction "GND_5") (pintype "power_in"))
      (node (ref "Y1") (pin "2") (pinfunction "GND_2") (pintype "power_in"))
      (node (ref "Y1") (pin "4") (pinfunction "GND_4") (pintype "power_in"))
    )
    (net (code "7") (name "IA611_IRQ") (class "Default")
      (node (ref "U2") (pin "9") (pinfunction "GPIO6_9") (pintype "bidirectional"))
      (node (ref "U5") (pin "17") (pinfunction "B3_17") (pintype "bidirectional"))
    )
    (net (code "8") (name "IA611_IRQ_LP") (class "Default")
      (node (ref "MK1") (pin "6") (pinfunction "P3_6") (pintype "bidirectional"))
      (node (ref "U5") (pin "4") (pinfunction "A3_4") (pintype "bidirectional"))
    )
    (net (code "9") (name "LSM6_INT1") (class "Default")
      (node (ref "U2") (pin "19") (pinfunction "GPIO15_19") (pintype "bidirectional"))
      (node (ref "U6") (pin "4") (pinfunction "INT1_4") (pintype "bidirectional"))
    )
    (net (code "10") (name "LSM6_INT2") (class "Default")
      (node (ref "U2") (pin "27") (pinfunction "GPIO16_27") (pintype "bidirectional"))
      (node (ref "U6") (pin "9") (pinfunction "INT2_9") (pintype "bidirectional"))
    )
    (net (code "11") (name "NPXL_1_IN") (class "Default")
      (node (ref "D1") (pin "4") (pinfunction "DIN_4") (pintype "input"))
      (node (ref "U2") (pin "13") (pinfunction "GPIO9_13") (pintype "bidirectional"))
    )
    (net (code "12") (name "NPXL_1_OUT") (class "Default")
      (node (ref "D1") (pin "2") (pinfunction "DOUT_2") (pintype "output"))
      (node (ref "D2") (pin "4") (pinfunction "DIN_4") (pintype "input"))
    )
    (net (code "13") (name "NPXL_2_OUT") (class "Default")
      (node (ref "D2") (pin "2") (pinfunction "DOUT_2") (pintype "output"))
      (node (ref "D3") (pin "4") (pinfunction "DIN_4") (pintype "input"))
    )
    (net (code "14") (name "NPXL_3_OUT") (class "Default")
      (node (ref "D3") (pin "2") (pinfunction "DOUT_2") (pintype "output"))
      (node (ref "D4") (pin "4") (pinfunction "DIN_4") (pintype "input"))
    )
    (net (code "15") (name "NPXL_4_OUT") (class "Default")
      (node (ref "D4") (pin "2") (pinfunction "DOUT_2") (pintype "output"))
      (node (ref "D5") (pin "4") (pinfunction "DIN_4") (pintype "input"))
    )
    (net (code "16") (name "NPXL_5_OUT") (class "Default")
      (node (ref "D5") (pin "2") (pinfunction "DOUT_2") (pintype "output"))
      (node (ref "D6") (pin "4") (pinfunction "DIN_4") (pintype "input"))
    )
    (net (code "17") (name "Net-(CONN1-CC1)") (class "Default")
      (node (ref "CONN1") (pin "A5") (pinfunction "CC1_A5") (pintype "bidirectional"))
      (node (ref "R3") (pin "2") (pinfunction "2_2") (pintype "passive"))
    )
    (net (code "18") (name "Net-(CONN1-CC2)") (class "Default")
      (node (ref "CONN1") (pin "B5") (pinfunction "CC2_B5") (pintype "bidirectional"))
      (node (ref "R8") (pin "2") (pinfunction "2_2") (pintype "passive"))
    )
    (net (code "19") (name "Net-(D11-PadA)") (class "Default")
      (node (ref "D11") (pin "A") (pinfunction "A_A") (pintype "passive"))
      (node (ref "R2") (pin "2") (pinfunction "2_2") (pintype "passive"))
    )
    (net (code "20") (name "Net-(D13-PadA)") (class "Default")
      (node (ref "D13") (pin "A") (pinfunction "A_A") (pintype "passive"))
      (node (ref "R16") (pin "1") (pinfunction "1_1") (pintype "passive"))
    )
    (net (code "21") (name "Net-(D14-PadA)") (class "Default")
      (node (ref "D14") (pin "A") (pinfunction "A_A") (pintype "passive"))
      (node (ref "R18") (pin "1") (pinfunction "1_1") (pintype "passive"))
    )
    (net (code "22") (name "Net-(D15-PadA)") (class "Default")
      (node (ref "D15") (pin "A") (pinfunction "A_A") (pintype "passive"))
      (node (ref "R19") (pin "1") (pinfunction "1_1") (pintype "passive"))
    )
    (net (code "23") (name "Net-(L3-P$1)") (class "Default")
      (node (ref "L3") (pin "1") (pinfunction "P$1_1") (pintype "bidirectional"))
      (node (ref "U4") (pin "2") (pinfunction "L2_2") (pintype "bidirectional"))
    )
    (net (code "24") (name "Net-(L3-P$2)") (class "Default")
      (node (ref "L3") (pin "2") (pinfunction "P$2_2") (pintype "bidirectional"))
      (node (ref "U4") (pin "4") (pinfunction "L1_4") (pintype "bidirectional"))
    )
    (net (code "25") (name "Net-(LS1-N)") (class "Default")
      (node (ref "D12") (pin "A") (pinfunction "A_A") (pintype "passive"))
      (node (ref "LS1") (pin "2") (pinfunction "N_2") (pintype "passive"))
      (node (ref "Q2") (pin "3") (pinfunction "D_3") (pintype "bidirectional"))
    )
    (net (code "26") (name "Net-(MK1-LDOD)") (class "Default")
      (node (ref "C44") (pin "1") (pinfunction "1_1") (pintype "passive"))
      (node (ref "MK1") (pin "2") (pinfunction "LDOD_2") (pintype "output"))
    )
    (net (code "27") (name "Net-(Q2-G)") (class "Default")
      (node (ref "Q2") (pin "1") (pinfunction "G_1") (pintype "bidirectional"))
      (node (ref "R25") (pin "1") (pinfunction "1_1") (pintype "passive"))
    )
    (net (code "28") (name "Net-(U2-GPIO8)") (class "Default")
      (node (ref "R2") (pin "1") (pinfunction "1_1") (pintype "passive"))
      (node (ref "U2") (pin "12") (pinfunction "GPIO8_12") (pintype "bidirectional"))
    )
    (net (code "29") (name "Net-(U2-VREG_AVDD)") (class "Default")
      (node (ref "C35") (pin "1") (pinfunction "1_1") (pintype "passive"))
      (node (ref "R11") (pin "2") (pinfunction "2_2") (pintype "passive"))
      (node (ref "U2") (pin "46") (pinfunction "VREG_AVDD_46") (pintype "bidirectional"))
    )
    (net (code "30") (name "Net-(U2-VREG_LX)") (class "Default")
      (node (ref "L2") (pin "1") (pinfunction "1_1") (pintype "passive"))
      (node (ref "U2") (pin "48") (pinfunction "VREG_LX_48") (pintype "bidirectional"))
    )
    (net (code "31") (name "Net-(U2-XIN)") (class "Default")
      (node (ref "C42") (pin "1") (pinfunction "1_1") (pintype "passive"))
      (node (ref "U2") (pin "21") (pinfunction "XIN_21") (pintype "bidirectional"))
      (node (ref "Y1") (pin "1") (pinfunction "1_1") (pintype "passive"))
    )
    (net (code "32") (name "Net-(U2-XOUT)") (class "Default")
      (node (ref "R15") (pin "2") (pinfunction "2_2") (pintype "passive"))
      (node (ref "U2") (pin "22") (pinfunction "XOUT_22") (pintype "bidirectional"))
    )
    (net (code "33") (name "Net-(U4-EN)") (class "Default")
      (node (ref "C24") (pin "1") (pinfunction "1_1") (pintype "passive"))
      (node (ref "R21") (pin "1") (pinfunction "1_1") (pintype "passive"))
      (node (ref "U4") (pin "6") (pinfunction "EN_6") (pintype "input"))
      (node (ref "U4") (pin "7") (pinfunction "PS/SYNC_7") (pintype "input"))
      (node (ref "U4") (pin "8") (pinfunction "VINA_8") (pintype "input"))
    )
    (net (code "34") (name "Net-(U5-OE)") (class "Default")
      (node (ref "R22") (pin "2") (pinfunction "2_2") (pintype "passive"))
      (node (ref "U5") (pin "10") (pinfunction "OE_10") (pintype "input"))
    )
    (net (code "35") (name "Net-(U7-PROG)") (class "Default")
      (node (ref "R20") (pin "2") (pinfunction "2_2") (pintype "passive"))
      (node (ref "U7") (pin "6") (pinfunction "PROG_6") (pintype "passive"))
    )
    (net (code "36") (name "Net-(U7-STAT2)") (class "Default")
      (node (ref "D15") (pin "C") (pinfunction "C_C") (pintype "passive"))
      (node (ref "U7") (pin "4") (pinfunction "STAT2_4") (pintype "output"))
    )
    (net (code "37") (name "Net-(U7-THERM)") (class "Default")
      (node (ref "R17") (pin "2") (pinfunction "2_2") (pintype "bidirectional"))
      (node (ref "U7") (pin "8") (pinfunction "THERM_8") (pintype "input"))
    )
    (net (code "38") (name "Net-(U7-~{PG})") (class "Default")
      (node (ref "D14") (pin "C") (pinfunction "C_C") (pintype "passive"))
      (node (ref "U7") (pin "7") (pinfunction "~{PG}_7") (pintype "output"))
    )
    (net (code "39") (name "Net-(U8-ILIM)") (class "Default")
      (node (ref "R14") (pin "2") (pinfunction "2_2") (pintype "passive"))
      (node (ref "U8") (pin "4") (pinfunction "ILIM_4") (pintype "input"))
    )
    (net (code "40") (name "Net-(U8-STAT)") (class "Default")
      (node (ref "D13") (pin "C") (pinfunction "C_C") (pintype "passive"))
      (node (ref "U8") (pin "1") (pinfunction "STAT_1") (pintype "output"))
    )
    (net (code "41") (name "Net-(U8-VSNS)") (class "Default")
      (node (ref "R10") (pin "1") (pinfunction "1_1") (pintype "passive"))
      (node (ref "R9") (pin "2") (pinfunction "2_2") (pintype "passive"))
      (node (ref "U8") (pin "3") (pinfunction "VSNS_3") (pintype "power_in"))
    )
    (net (code "42") (name "Net-(Y1-2)") (class "Default")
      (node (ref "C41") (pin "1") (pinfunction "1_1") (pintype "passive"))
      (node (ref "R15") (pin "1") (pinfunction "1_1") (pintype "passive"))
      (node (ref "Y1") (pin "3") (pinfunction "2_3") (pintype "passive"))
    )
    (net (code "43") (name "PDM_CLK") (class "Default")
      (node (ref "U2") (pin "5") (pinfunction "GPIO3_5") (pintype "bidirectional"))
      (node (ref "U5") (pin "20") (pinfunction "B1_20") (pintype "bidirectional"))
    )
    (net (code "44") (name "PDM_CLK_LP") (class "Default")
      (node (ref "MK1") (pin "3") (pinfunction "P0_3") (pintype "bidirectional"))
      (node (ref "U5") (pin "1") (pinfunction "A1_1") (pintype "bidirectional"))
    )
    (net (code "45") (name "PDM_SDO") (class "Default")
      (node (ref "U2") (pin "4") (pinfunction "GPIO2_4") (pintype "bidirectional"))
      (node (ref "U5") (pin "18") (pinfunction "B2_18") (pintype "bidirectional"))
    )
    (net (code "46") (name "PDM_SDO_LP") (class "Default")
      (node (ref "MK1") (pin "5") (pinfunction "P1_5") (pintype "bidirectional"))
      (node (ref "U5") (pin "3") (pinfunction "A2_3") (pintype "bidirectional"))
    )
    (net (code "47") (name "QSPI_CLK") (class "Default")
      (node (ref "IC1") (pin "6") (pinfunction "CLK_6") (pintype "bidirectional"))
      (node (ref "U2") (pin "56") (pinfunction "QSPI_SCLK_56") (pintype "bidirectional"))
    )
    (net (code "48") (name "SCL") (class "Default")
      (node (ref "R7") (pin "1") (pinfunction "1_1") (pintype "passive"))
      (node (ref "U2") (pin "37") (pinfunction "GPIO25_37") (pintype "bidirectional"))
      (node (ref "U6") (pin "13") (pinfunction "SCL_13") (pintype "bidirectional"))
    )
    (net (code "49") (name "SDA") (class "Default")
      (node (ref "R6") (pin "1") (pinfunction "1_1") (pintype "passive"))
      (node (ref "U2") (pin "36") (pinfunction "GPIO24_36") (pintype "bidirectional"))
      (node (ref "U6") (pin "14") (pinfunction "SDA_14") (pintype "bidirectional"))
    )
    (net (code "50") (name "SIO0") (class "Default")
      (node (ref "IC1") (pin "5") (pinfunction "DI(IO0)_5") (pintype "bidirectional"))
      (node (ref "U2") (pin "57") (pinfunction "QSPI_SD0_57") (pintype "bidirectional"))
    )
    (net (code "51") (name "SIO1") (class "Default")
      (node (ref "IC1") (pin "2") (pinfunction "DO(IO1)_2") (pintype "bidirectional"))
      (node (ref "U2") (pin "59") (pinfunction "QSPI_SD1_59") (pintype "bidirectional"))
    )
    (net (code "52") (name "SIO2") (class "Default")
      (node (ref "IC1") (pin "3") (pinfunction "~{WP(IO2})_3") (pintype "bidirectional"))
      (node (ref "U2") (pin "58") (pinfunction "QSPI_SD2_58") (pintype "bidirectional"))
    )
    (net (code "53") (name "SIO3") (class "Default")
      (node (ref "IC1") (pin "7") (pinfunction "~{HOLD_OR_}RESET_(IO3)_7") (pintype "bidirectional"))
      (node (ref "U2") (pin "55") (pinfunction "QSPI_SD3_55") (pintype "bidirectional"))
    )
    (net (code "54") (name "SWCLK") (class "Default")
      (node (ref "J4") (pin "1") (pinfunction "1_1") (pintype "passive"))
      (node (ref "U2") (pin "24") (pinfunction "SWCLK_24") (pintype "bidirectional"))
    )
    (net (code "55") (name "SWDIO") (class "Default")
      (node (ref "J4") (pin "3") (pinfunction "3_3") (pintype "passive"))
      (node (ref "U2") (pin "25") (pinfunction "SWDIO_25") (pintype "bidirectional"))
    )
    (net (code "56") (name "UART_RX") (class "Default")
      (node (ref "U2") (pin "7") (pinfunction "GPIO4_7") (pintype "bidirectional"))
      (node (ref "U5") (pin "15") (pinfunction "B5_15") (pintype "bidirectional"))
    )
    (net (code "57") (name "UART_RX_LP") (class "Default")
      (node (ref "MK1") (pin "8") (pinfunction "P4_8") (pintype "bidirectional"))
      (node (ref "U5") (pin "6") (pinfunction "A5_6") (pintype "bidirectional"))
    )
    (net (code "58") (name "UART_TX") (class "Default")
      (node (ref "U2") (pin "8") (pinfunction "GPIO5_8") (pintype "bidirectional"))
      (node (ref "U5") (pin "16") (pinfunction "B4_16") (pintype "bidirectional"))
    )
    (net (code "59") (name "UART_TX_LP") (class "Default")
      (node (ref "MK1") (pin "9") (pinfunction "P5_9") (pintype "bidirectional"))
      (node (ref "U5") (pin "5") (pinfunction "A4_5") (pintype "bidirectional"))
    )
    (net (code "60") (name "USB_N") (class "Default")
      (node (ref "CONN1") (pin "A7") (pinfunction "DN1_A7") (pintype "bidirectional"))
      (node (ref "CONN1") (pin "B7") (pinfunction "DN2_B7") (pintype "bidirectional"))
      (node (ref "R13") (pin "1") (pinfunction "1_1") (pintype "passive"))
    )
    (net (code "61") (name "USB_P") (class "Default")
      (node (ref "CONN1") (pin "A6") (pinfunction "DP1_A6") (pintype "bidirectional"))
      (node (ref "CONN1") (pin "B6") (pinfunction "DP2_B6") (pintype "bidirectional"))
      (node (ref "R12") (pin "1") (pinfunction "1_1") (pintype "passive"))
    )
    (net (code "62") (name "U_N") (class "Default")
      (node (ref "R13") (pin "2") (pinfunction "2_2") (pintype "passive"))
      (node (ref "U2") (pin "51") (pinfunction "USB_D-_51") (pintype "bidirectional"))
    )
    (net (code "63") (name "U_P") (class "Default")
      (node (ref "R12") (pin "2") (pinfunction "2_2") (pintype "passive"))
      (node (ref "U2") (pin "52") (pinfunction "USB_D+_52") (pintype "bidirectional"))
    )
    (net (code "64") (name "VBUS") (class "Default")
      (node (ref "C12") (pin "1") (pinfunction "1_1") (pintype "passive"))
      (node (ref "CONN1") (pin "A4_B9") (pinfunction "VBUS_A4_B9") (pintype "power_in"))
      (node (ref "CONN1") (pin "B4_A9") (pinfunction "VBUS_B4_A9") (pintype "power_in"))
      (node (ref "L1") (pin "1") (pinfunction "1_1") (pintype "passive"))
    )
    (net (code "65") (name "VIN") (class "Default")
      (node (ref "C23") (pin "1") (pinfunction "1_1") (pintype "passive"))
      (node (ref "R21") (pin "2") (pinfunction "2_2") (pintype "passive"))
      (node (ref "U4") (pin "5") (pinfunction "VIN_5") (pintype "input"))
      (node (ref "U8") (pin "7") (pinfunction "OUT_7") (pintype "output"))
    )
    (net (code "66") (name "V_BATT") (class "Default")
      (node (ref "C15") (pin "1") (pinfunction "1_1") (pintype "passive"))
      (node (ref "C20") (pin "1") (pinfunction "1_1") (pintype "passive"))
      (node (ref "J1") (pin "2") (pinfunction "+_2") (pintype "bidirectional"))
      (node (ref "U7") (pin "10") (pinfunction "VBAT_10") (pintype "output"))
      (node (ref "U7") (pin "9") (pinfunction "VBAT_9") (pintype "output"))
      (node (ref "U8") (pin "6") (pinfunction "IN2_6") (pintype "input"))
    )
    (net (code "67") (name "V_USB") (class "Default")
      (node (ref "C13") (pin "1") (pinfunction "1_1") (pintype "passive"))
      (node (ref "C14") (pin "2") (pinfunction "2_2") (pintype "passive"))
      (node (ref "C16") (pin "2") (pinfunction "2_2") (pintype "passive"))
      (node (ref "L1") (pin "2") (pinfunction "2_2") (pintype "passive"))
      (node (ref "R16") (pin "2") (pinfunction "2_2") (pintype "passive"))
      (node (ref "R18") (pin "2") (pinfunction "2_2") (pintype "passive"))
      (node (ref "R19") (pin "2") (pinfunction "2_2") (pintype "passive"))
      (node (ref "R9") (pin "1") (pinfunction "1_1") (pintype "passive"))
      (node (ref "U7") (pin "1") (pinfunction "VDD_1") (pintype "power_in"))
      (node (ref "U7") (pin "2") (pinfunction "VDD_2") (pintype "power_in"))
      (node (ref "U8") (pin "8") (pinfunction "IN1_8") (pintype "input"))
    )
    (net (code "68") (name "unconnected-(CONN1-SBU1-PadA8)") (class "Default")
      (node (ref "CONN1") (pin "A8") (pinfunction "SBU1_A8") (pintype "bidirectional"))
    )
    (net (code "69") (name "unconnected-(CONN1-SBU2-PadB8)") (class "Default")
      (node (ref "CONN1") (pin "B8") (pinfunction "SBU2_B8") (pintype "bidirectional"))
    )
    (net (code "70") (name "unconnected-(D6-DOUT-Pad2)") (class "Default")
      (node (ref "D6") (pin "2") (pinfunction "DOUT_2") (pintype "output"))
    )
    (net (code "71") (name "unconnected-(J1-PAD1-PadNC1)") (class "Default")
      (node (ref "J1") (pin "NC1") (pinfunction "PAD1_NC1") (pintype "bidirectional"))
    )
    (net (code "72") (name "unconnected-(J1-PAD2-PadNC2)") (class "Default")
      (node (ref "J1") (pin "NC2") (pinfunction "PAD2_NC2") (pintype "bidirectional"))
    )
    (net (code "73") (name "unconnected-(MK1-P2-Pad4)") (class "Default")
      (node (ref "MK1") (pin "4") (pinfunction "P2_4") (pintype "bidirectional"))
    )
    (net (code "74") (name "unconnected-(U2-GPIO0-Pad2)") (class "Default")
      (node (ref "U2") (pin "2") (pinfunction "GPIO0_2") (pintype "bidirectional"))
    )
    (net (code "75") (name "unconnected-(U2-GPIO7-Pad10)") (class "Default")
      (node (ref "U2") (pin "10") (pinfunction "GPIO7_10") (pintype "bidirectional"))
    )
    (net (code "76") (name "unconnected-(U2-GPIO11-Pad15)") (class "Default")
      (node (ref "U2") (pin "15") (pinfunction "GPIO11_15") (pintype "bidirectional"))
    )
    (net (code "77") (name "unconnected-(U2-GPIO12-Pad16)") (class "Default")
      (node (ref "U2") (pin "16") (pinfunction "GPIO12_16") (pintype "bidirectional"))
    )
    (net (code "78") (name "unconnected-(U2-GPIO13-Pad17)") (class "Default")
      (node (ref "U2") (pin "17") (pinfunction "GPIO13_17") (pintype "bidirectional"))
    )
    (net (code "79") (name "unconnected-(U2-GPIO14-Pad18)") (class "Default")
      (node (ref "U2") (pin "18") (pinfunction "GPIO14_18") (pintype "bidirectional"))
    )
    (net (code "80") (name "unconnected-(U2-GPIO17-Pad28)") (class "Default")
      (node (ref "U2") (pin "28") (pinfunction "GPIO17_28") (pintype "bidirectional"))
    )
    (net (code "81") (name "unconnected-(U2-GPIO18-Pad29)") (class "Default")
      (node (ref "U2") (pin "29") (pinfunction "GPIO18_29") (pintype "bidirectional"))
    )
    (net (code "82") (name "unconnected-(U2-GPIO19-Pad31)") (class "Default")
      (node (ref "U2") (pin "31") (pinfunction "GPIO19_31") (pintype "bidirectional"))
    )
    (net (code "83") (name "unconnected-(U2-GPIO20-Pad32)") (class "Default")
      (node (ref "U2") (pin "32") (pinfunction "GPIO20_32") (pintype "bidirectional"))
    )
    (net (code "84") (name "unconnected-(U2-GPIO21-Pad33)") (class "Default")
      (node (ref "U2") (pin "33") (pinfunction "GPIO21_33") (pintype "bidirectional"))
    )
    (net (code "85") (name "unconnected-(U2-GPIO22-Pad34)") (class "Default")
      (node (ref "U2") (pin "34") (pinfunction "GPIO22_34") (pintype "bidirectional"))
    )
    (net (code "86") (name "unconnected-(U2-GPIO23-Pad35)") (class "Default")
      (node (ref "U2") (pin "35") (pinfunction "GPIO23_35") (pintype "bidirectional"))
    )
    (net (code "87") (name "unconnected-(U2-GPIO26{slash}ADC0-Pad40)") (class "Default")
      (node (ref "U2") (pin "40") (pinfunction "GPIO26/ADC0_40") (pintype "bidirectional"))
    )
    (net (code "88") (name "unconnected-(U2-GPIO27{slash}ADC1-Pad41)") (class "Default")
      (node (ref "U2") (pin "41") (pinfunction "GPIO27/ADC1_41") (pintype "bidirectional"))
    )
    (net (code "89") (name "unconnected-(U2-GPIO28{slash}ADC2-Pad42)") (class "Default")
      (node (ref "U2") (pin "42") (pinfunction "GPIO28/ADC2_42") (pintype "bidirectional"))
    )
    (net (code "90") (name "unconnected-(U2-GPIO29{slash}ADC3-Pad43)") (class "Default")
      (node (ref "U2") (pin "43") (pinfunction "GPIO29/ADC3_43") (pintype "bidirectional"))
    )
    (net (code "91") (name "unconnected-(U5-A6-Pad7)") (class "Default")
      (node (ref "U5") (pin "7") (pinfunction "A6_7") (pintype "bidirectional"))
    )
    (net (code "92") (name "unconnected-(U5-A7-Pad8)") (class "Default")
      (node (ref "U5") (pin "8") (pinfunction "A7_8") (pintype "bidirectional"))
    )
    (net (code "93") (name "unconnected-(U5-A8-Pad9)") (class "Default")
      (node (ref "U5") (pin "9") (pinfunction "A8_9") (pintype "bidirectional"))
    )
    (net (code "94") (name "unconnected-(U5-B6-Pad14)") (class "Default")
      (node (ref "U5") (pin "14") (pinfunction "B6_14") (pintype "bidirectional"))
    )
    (net (code "95") (name "unconnected-(U5-B7-Pad13)") (class "Default")
      (node (ref "U5") (pin "13") (pinfunction "B7_13") (pintype "bidirectional"))
    )
    (net (code "96") (name "unconnected-(U5-B8-Pad12)") (class "Default")
      (node (ref "U5") (pin "12") (pinfunction "B8_12") (pintype "bidirectional"))
    )
    (net (code "97") (name "~{BOOT}") (class "Default")
      (node (ref "R5") (pin "2") (pinfunction "2_2") (pintype "passive"))
      (node (ref "S1") (pin "1") (pinfunction "1_1") (pintype "passive"))
      (node (ref "S1") (pin "2") (pinfunction "1_2") (pintype "passive"))
    )
    (net (code "98") (name "~{QSPI_CS}") (class "Default")
      (node (ref "IC1") (pin "1") (pinfunction "~{CS}_1") (pintype "bidirectional"))
      (node (ref "R4") (pin "1") (pinfunction "1_1") (pintype "passive"))
      (node (ref "R5") (pin "1") (pinfunction "1_1") (pintype "passive"))
      (node (ref "U2") (pin "60") (pinfunction "QSPI_~{CS}_60") (pintype "bidirectional"))
    )
    (net (code "99") (name "~{RESET}") (class "Default")
      (node (ref "S2") (pin "1") (pinfunction "1_1") (pintype "passive"))
      (node (ref "S2") (pin "2") (pinfunction "1_2") (pintype "passive"))
      (node (ref "U2") (pin "26") (pinfunction "RUN_26") (pintype "bidirectional"))
    )
  )
)
